# lora.net
KiCad netlist of a schematic drawn in Altium Designer
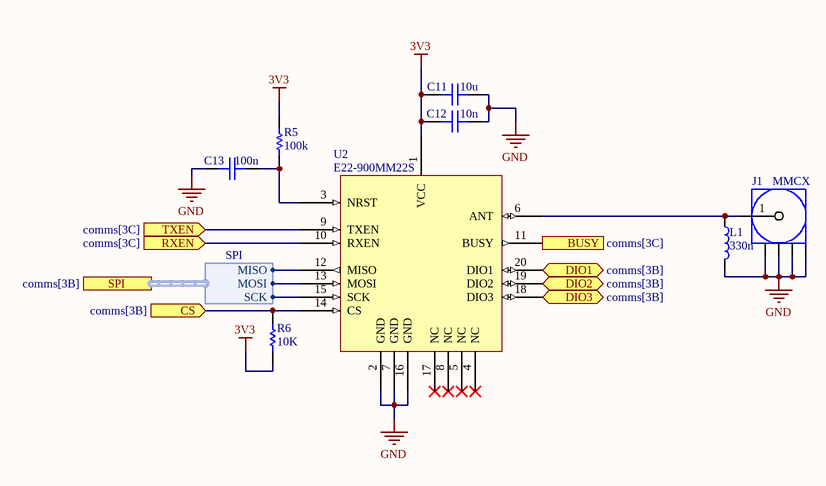
[diagram p0: lora.SchDoc]

(export (version "E")
  (design (tool "Eeschema 10.0.6"))
  (components
    (comp (ref "C11")
      (value "10u")
      (description "Capacitor")
      (libsource (lib "drfc_schlib") (part "Capacitor"))
    )
    (comp (ref "C12")
      (value "10n")
      (description "Capacitor")
      (libsource (lib "drfc_schlib") (part "Capacitor"))
    )
    (comp (ref "C13")
      (value "100n")
      (description "Capacitor")
      (libsource (lib "drfc_schlib") (part "Capacitor"))
    )
    (comp (ref "J1")
      (value "MMCX")
      (description "Coaxial Connector")
      (libsource (lib "drfc_schlib") (part "Conn_Coaxial"))
    )
    (comp (ref "L1")
      (value "330n")
      (description "Inductor")
      (libsource (lib "drfc_schlib") (part "Inductor"))
    )
    (comp (ref "R5")
      (value "100k")
      (description "Resistor")
      (libsource (lib "drfc_schlib") (part "Resistor"))
    )
    (comp (ref "R6") (value "10K") (description "Resistor") (libsource (lib "drfc_schlib") (part "Resistor")))
    (comp (ref "U2")
      (value "E22-900MM22S")
      (description "SX1262 868/915MHz ultra small size Lora SMD module")
      (libsource (lib "drfc_schlib") (part "E22-900MM22S"))
    )
  )
  (nets
    (net (code "2") (name "/BUSY") (class "Default")
      (node (ref "U2") (pin "11") (pinfunction "BUSY_11") (pintype "output"))
    )
    (net (code "3") (name "/CS") (class "Default")
      (node (ref "R6") (pin "2") (pinfunction "2_2") (pintype "passive"))
      (node (ref "U2") (pin "14") (pinfunction "CS_14") (pintype "input"))
    )
    (net (code "4") (name "/DIO1") (class "Default")
      (node (ref "U2") (pin "20") (pinfunction "DIO1_20") (pintype "bidirectional"))
    )
    (net (code "5") (name "/DIO2") (class "Default")
      (node (ref "U2") (pin "19") (pinfunction "DIO2_19") (pintype "bidirectional"))
    )
    (net (code "6") (name "/DIO3") (class "Default")
      (node (ref "U2") (pin "18") (pinfunction "DIO3_18") (pintype "bidirectional"))
    )
    (net (code "7") (name "/MISO") (class "Default")
      (node (ref "U2") (pin "12") (pinfunction "MISO_12") (pintype "output"))
    )
    (net (code "8") (name "/MOSI") (class "Default")
      (node (ref "U2") (pin "13") (pinfunction "MOSI_13") (pintype "input"))
    )
    (net (code "9") (name "/RXEN") (class "Default")
      (node (ref "U2") (pin "10") (pinfunction "RXEN_10") (pintype "input"))
    )
    (net (code "10") (name "/SCK") (class "Default")
      (node (ref "U2") (pin "15") (pinfunction "SCK_15") (pintype "input"))
    )
    (net (code "11") (name "/TXEN") (class "Default")
      (node (ref "U2") (pin "9") (pinfunction "TXEN_9") (pintype "input"))
    )
    (net (code "13") (name "3V3") (class "Default")
      (node (ref "C11") (pin "2") (pinfunction "2_2") (pintype "passive"))
      (node (ref "C12") (pin "2") (pinfunction "2_2") (pintype "passive"))
      (node (ref "R5") (pin "2") (pinfunction "2_2") (pintype "passive"))
      (node (ref "R6") (pin "1") (pinfunction "1_1") (pintype "passive"))
      (node (ref "U2") (pin "1") (pinfunction "VCC_1") (pintype "power_in"))
    )
    (net (code "14") (name "GND") (class "Default")
      (node (ref "C11") (pin "1") (pinfunction "1_1") (pintype "passive"))
      (node (ref "C12") (pin "1") (pinfunction "1_1") (pintype "passive"))
      (node (ref "C13") (pin "2") (pinfunction "2_2") (pintype "passive"))
      (node (ref "J1") (pin "2") (pinfunction "2_2") (pintype "power_in"))
      (node (ref "J1") (pin "3") (pinfunction "3_3") (pintype "power_in"))
      (node (ref "J1") (pin "4") (pinfunction "4_4") (pintype "power_in"))
      (node (ref "J1") (pin "5") (pinfunction "5_5") (pintype "power_in"))
      (node (ref "L1") (pin "2") (pinfunction "2_2") (pintype "passive"))
      (node (ref "U2") (pin "16") (pinfunction "GND_16") (pintype "power_in"))
      (node (ref "U2") (pin "2") (pinfunction "GND_2") (pintype "power_in"))
      (node (ref "U2") (pin "7") (pinfunction "GND_7") (pintype "power_in"))
    )
    (net (code "15") (name "Net-(U2-ANT)") (class "Default")
      (node (ref "J1") (pin "1") (pinfunction "1_1") (pintype "passive"))
      (node (ref "L1") (pin "1") (pinfunction "1_1") (pintype "passive"))
      (node (ref "U2") (pin "6") (pinfunction "ANT_6") (pintype "bidirectional"))
    )
    (net (code "16") (name "Net-(U2-NRST)") (class "Default")
      (node (ref "C13") (pin "1") (pinfunction "1_1") (pintype "passive"))
      (node (ref "R5") (pin "1") (pinfunction "1_1") (pintype "passive"))
      (node (ref "U2") (pin "3") (pinfunction "NRST_3") (pintype "input"))
    )
    (net (code "17") (name "unconnected-(U2-NC-Pad4)") (class "Default")
      (node (ref "U2") (pin "4") (pinfunction "NC_4") (pintype "open_collector+no_connect"))
    )
    (net (code "18") (name "unconnected-(U2-NC-Pad5)") (class "Default")
      (node (ref "U2") (pin "5") (pinfunction "NC_5") (pintype "open_collector+no_connect"))
    )
    (net (code "19") (name "unconnected-(U2-NC-Pad8)") (class "Default")
      (node (ref "U2") (pin "8") (pinfunction "NC_8") (pintype "open_collector+no_connect"))
    )
    (net (code "20") (name "unconnected-(U2-NC-Pad17)") (class "Default")
      (node (ref "U2") (pin "17") (pinfunction "NC_17") (pintype "open_collector+no_connect"))
    )
  )
)
